# MEMS.net
KiCad netlist of a schematic drawn in Altium Designer
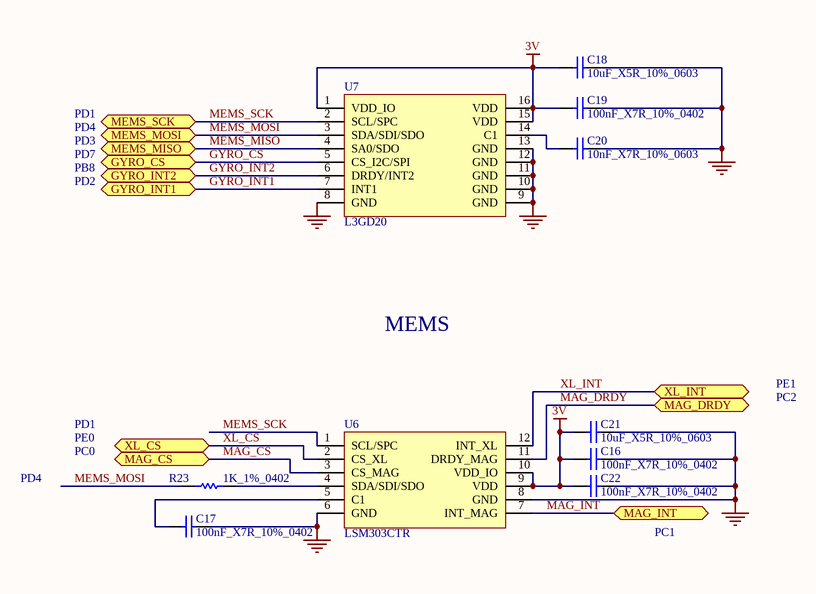
[diagram p0: MEMS.SchDoc]

(export (version "E")
  (design (tool "Eeschema 10.0.6"))
  (components
    (comp (ref "C16")
      (value "100nF_X7R_10%_0402")
      (footprint "0402C")
      (description "Capacitor,100nF,16V,X7R,10%,0402,YAGEO")
      (libsource (lib "MCD_TOOLS") (part "Cap_100nF_X7R_10%_0402"))
    )
    (comp (ref "C17")
      (value "100nF_X7R_10%_0402")
      (footprint "0402C")
      (description "Capacitor,100nF,16V,X7R,10%,0402,YAGEO")
      (libsource (lib "MCD_TOOLS") (part "Cap_100nF_X7R_10%_0402"))
    )
    (comp (ref "C18")
      (value "10uF_X5R_10%_0603")
      (footprint "0603C")
      (description "Capacitor,10uF,6.3V,X5R,10%,0603,YAGEO")
      (libsource (lib "MCD_TOOLS") (part "Cap_10uF_X5R_10%_0603"))
    )
    (comp (ref "C19")
      (value "100nF_X7R_10%_0402")
      (footprint "0402C")
      (description "Capacitor,100nF,16V,X7R,10%,0402,YAGEO")
      (libsource (lib "MCD_TOOLS") (part "Cap_100nF_X7R_10%_0402"))
    )
    (comp (ref "C20")
      (value "10nF_X7R_10%_0603")
      (footprint "0603C")
      (description "Capacitor,10nF,50V,X7R,10%,0603,YAGEO")
      (libsource (lib "MCD_TOOLS") (part "Cap_10nF_X7R_10%_0603"))
    )
    (comp (ref "C21")
      (value "10uF_X5R_10%_0603")
      (footprint "0603C")
      (description "Capacitor,10uF,6.3V,X5R,10%,0603,YAGEO")
      (libsource (lib "MCD_TOOLS") (part "Cap_10uF_X5R_10%_0603"))
    )
    (comp (ref "C22")
      (value "100nF_X7R_10%_0402")
      (footprint "0402C")
      (description "Capacitor,100nF,16V,X7R,10%,0402,YAGEO")
      (libsource (lib "MCD_TOOLS") (part "Cap_100nF_X7R_10%_0402"))
    )
    (comp (ref "R23")
      (value "1K_1%_0402")
      (footprint "0402R")
      (description "Resistor,1K,0402,1%,YAGEO")
      (libsource (lib "MCD_TOOLS") (part "Res_1K_1%_0402"))
    )
    (comp (ref "U6")
      (value "LSM303CTR")
      (footprint "LGA12_2x2")
      (description "Ultra compact high performance e-compass 3D accelerometer and 3D magnetometer module")
      (libsource (lib "MCD_TOOLS") (part "LSM303CTR"))
    )
    (comp (ref "U7") (value "L3GD20") (footprint "LGA16-4x4") (libsource (lib "MCD_TOOLS") (part "L3GD20")))
  )
  (nets
    (net (code "1") (name "/GYRO_CS") (class "Default")
      (node (ref "U7") (pin "5") (pinfunction "CS_I2C/SPI_5") (pintype "passive"))
    )
    (net (code "2") (name "/GYRO_INT1") (class "Default")
      (node (ref "U7") (pin "7") (pinfunction "INT1_7") (pintype "passive"))
    )
    (net (code "3") (name "/GYRO_INT2") (class "Default")
      (node (ref "U7") (pin "6") (pinfunction "DRDY/INT2_6") (pintype "passive"))
    )
    (net (code "4") (name "/MAG_CS") (class "Default")
      (node (ref "U6") (pin "3") (pinfunction "CS_MAG_3") (pintype "passive"))
    )
    (net (code "5") (name "/MAG_DRDY") (class "Default")
      (node (ref "U6") (pin "11") (pinfunction "DRDY_MAG_11") (pintype "passive"))
    )
    (net (code "6") (name "/MAG_INT") (class "Default")
      (node (ref "U6") (pin "7") (pinfunction "INT_MAG_7") (pintype "passive"))
    )
    (net (code "7") (name "/MEMS_MISO") (class "Default")
      (node (ref "U7") (pin "4") (pinfunction "SA0/SDO_4") (pintype "passive"))
    )
    (net (code "8") (name "/MEMS_MOSI") (class "Default")
      (node (ref "R23") (pin "1") (pinfunction "1_1") (pintype "passive"))
      (node (ref "U7") (pin "3") (pinfunction "SDA/SDI/SDO_3") (pintype "passive"))
    )
    (net (code "9") (name "/MEMS_SCK") (class "Default")
      (node (ref "U6") (pin "1") (pinfunction "SCL/SPC_1") (pintype "passive"))
      (node (ref "U7") (pin "2") (pinfunction "SCL/SPC_2") (pintype "passive"))
    )
    (net (code "10") (name "/XL_CS") (class "Default")
      (node (ref "U6") (pin "2") (pinfunction "CS_XL_2") (pintype "passive"))
    )
    (net (code "11") (name "/XL_INT") (class "Default")
      (node (ref "U6") (pin "12") (pinfunction "INT_XL_12") (pintype "passive"))
    )
    (net (code "12") (name "3V") (class "Default")
      (node (ref "C16") (pin "1") (pinfunction "1_1") (pintype "passive"))
      (node (ref "C18") (pin "1") (pinfunction "1_1") (pintype "passive"))
      (node (ref "C19") (pin "1") (pinfunction "1_1") (pintype "passive"))
      (node (ref "C21") (pin "1") (pinfunction "1_1") (pintype "passive"))
      (node (ref "C22") (pin "1") (pinfunction "1_1") (pintype "passive"))
      (node (ref "U6") (pin "10") (pinfunction "VDD_IO_10") (pintype "passive"))
      (node (ref "U6") (pin "9") (pinfunction "VDD_9") (pintype "passive"))
      (node (ref "U7") (pin "1") (pinfunction "VDD_IO_1") (pintype "passive"))
      (node (ref "U7") (pin "15") (pinfunction "VDD_15") (pintype "passive"))
      (node (ref "U7") (pin "16") (pinfunction "VDD_16") (pintype "passive"))
    )
    (net (code "13") (name "GND") (class "Default")
      (node (ref "C16") (pin "2") (pinfunction "2_2") (pintype "passive"))
      (node (ref "C17") (pin "2") (pinfunction "2_2") (pintype "passive"))
      (node (ref "C18") (pin "2") (pinfunction "2_2") (pintype "passive"))
      (node (ref "C19") (pin "2") (pinfunction "2_2") (pintype "passive"))
      (node (ref "C20") (pin "2") (pinfunction "2_2") (pintype "passive"))
      (node (ref "C21") (pin "2") (pinfunction "2_2") (pintype "passive"))
      (node (ref "C22") (pin "2") (pinfunction "2_2") (pintype "passive"))
      (node (ref "U6") (pin "6") (pinfunction "GND_6") (pintype "passive"))
      (node (ref "U6") (pin "8") (pinfunction "GND_8") (pintype "passive"))
      (node (ref "U7") (pin "10") (pinfunction "GND_10") (pintype "passive"))
      (node (ref "U7") (pin "11") (pinfunction "GND_11") (pintype "passive"))
      (node (ref "U7") (pin "12") (pinfunction "GND_12") (pintype "passive"))
      (node (ref "U7") (pin "13") (pinfunction "GND_13") (pintype "passive"))
      (node (ref "U7") (pin "8") (pinfunction "GND_8") (pintype "passive"))
      (node (ref "U7") (pin "9") (pinfunction "GND_9") (pintype "passive"))
    )
    (net (code "14") (name "Net-(U6-C1)") (class "Default")
      (node (ref "C17") (pin "1") (pinfunction "1_1") (pintype "passive"))
      (node (ref "U6") (pin "5") (pinfunction "C1_5") (pintype "passive"))
    )
    (net (code "15") (name "Net-(U6-SDA{slash}SDI{slash}SDO)") (class "Default")
      (node (ref "R23") (pin "2") (pinfunction "2_2") (pintype "passive"))
      (node (ref "U6") (pin "4") (pinfunction "SDA/SDI/SDO_4") (pintype "passive"))
    )
    (net (code "16") (name "Net-(U7-C1)") (class "Default")
      (node (ref "C20") (pin "1") (pinfunction "1_1") (pintype "passive"))
      (node (ref "U7") (pin "14") (pinfunction "C1_14") (pintype "passive"))
    )
  )
)
